# mippe_base_v2.net
KiCad netlist of a schematic drawn in EAGLE
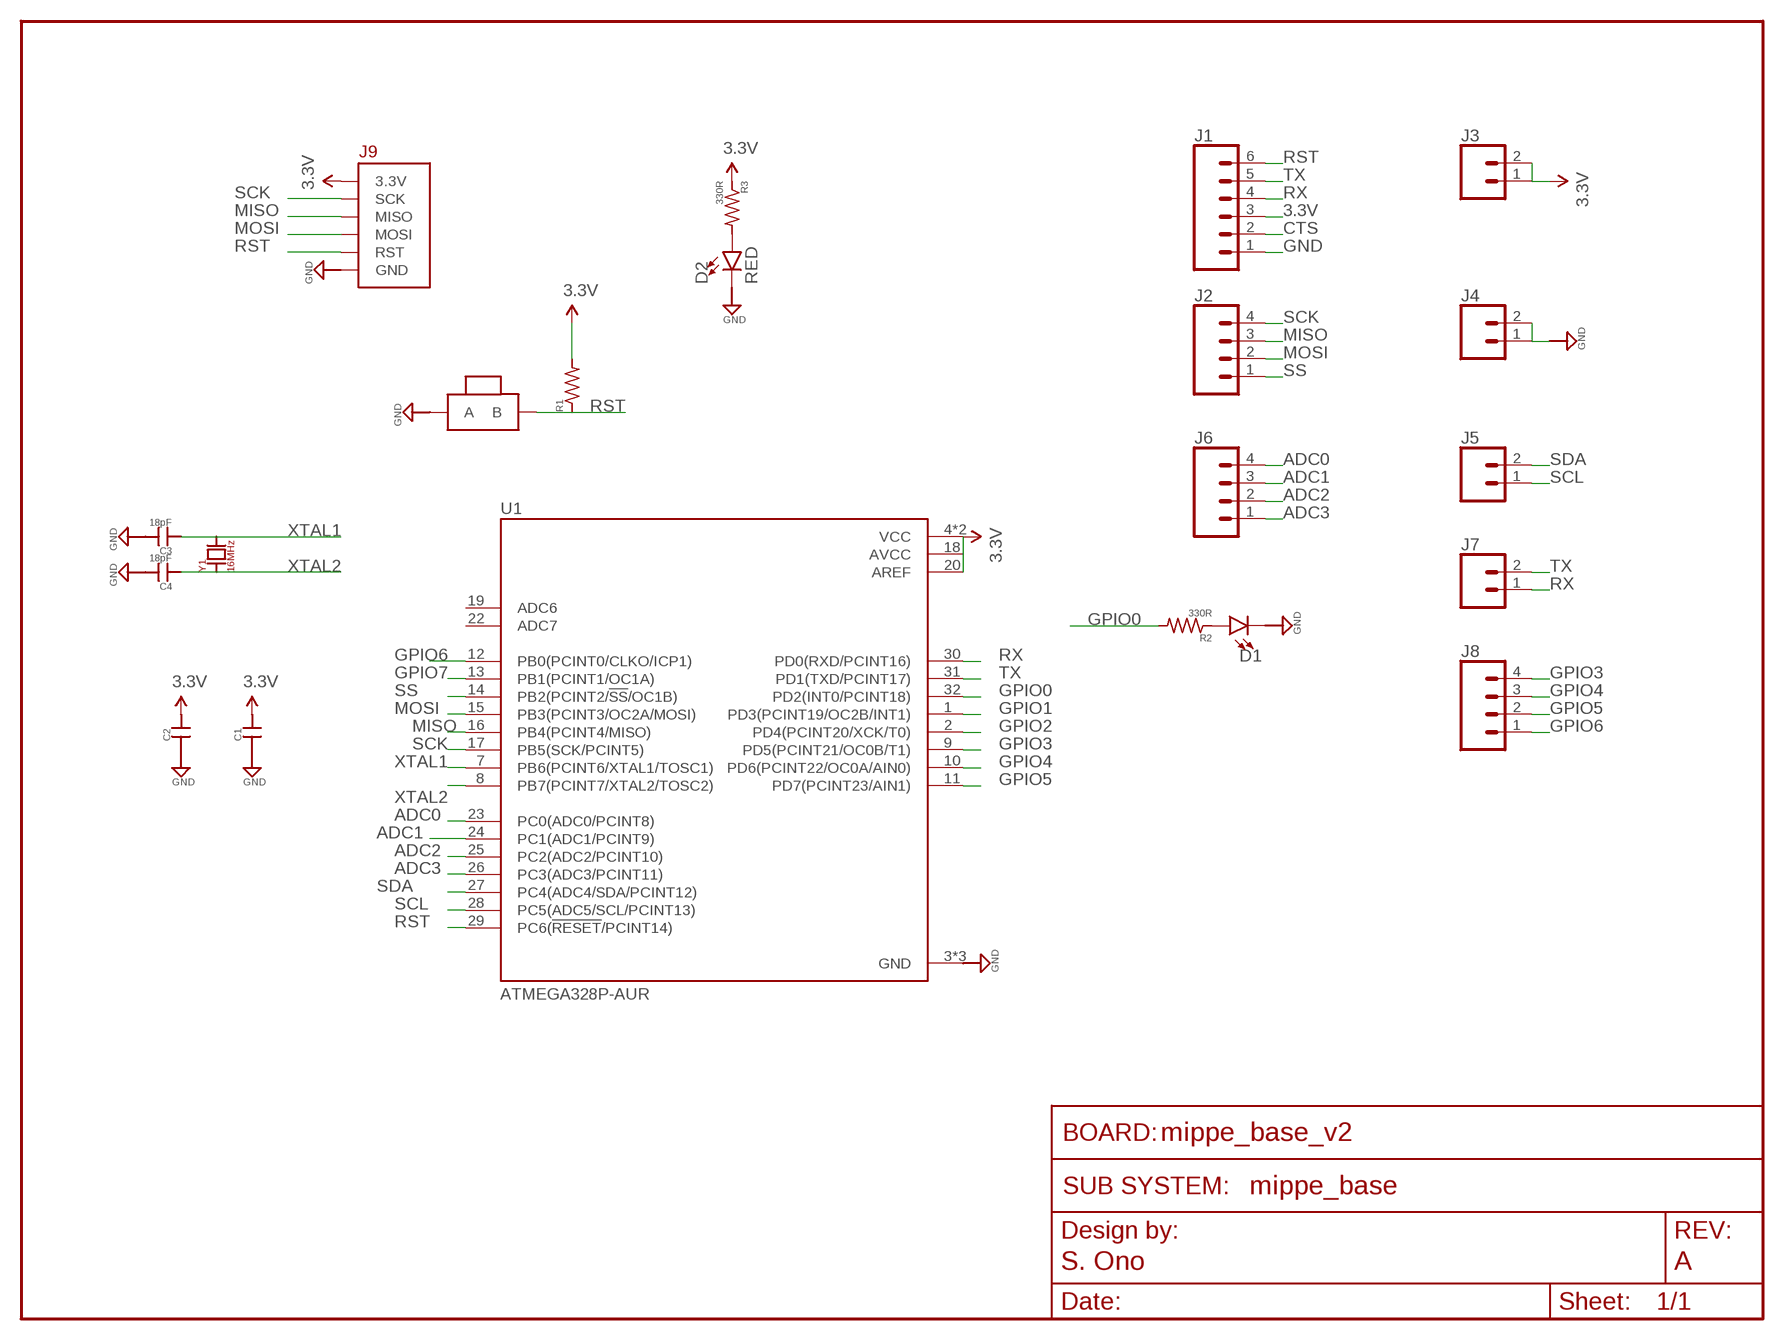
[diagram p0: schematic, sheet 1]

(export (version "E")
  (design (tool "Eeschema 10.0.6"))
  (components
    (comp (ref "C1")
      (value "CAP0603-CAP")
      (footprint "eagle-import:0603-CAP")
      (libsource (lib "eagle-import") (part "CAP0603-CAP"))
    )
    (comp (ref "C2")
      (value "CAP0603-CAP")
      (footprint "eagle-import:0603-CAP")
      (libsource (lib "eagle-import") (part "CAP0603-CAP"))
    )
    (comp (ref "C3")
      (value "18pF")
      (footprint "eagle-import:0603-CAP")
      (libsource (lib "eagle-import") (part "CAP0603-CAP"))
    )
    (comp (ref "C4")
      (value "18pF")
      (footprint "eagle-import:0603-CAP")
      (libsource (lib "eagle-import") (part "CAP0603-CAP"))
    )
    (comp (ref "D1")
      (value "LED0603")
      (footprint "eagle-import:LED-0603")
      (libsource (lib "eagle-import") (part "LED0603"))
    )
    (comp (ref "D2")
      (value "RED")
      (footprint "eagle-import:LED-0603")
      (libsource (lib "eagle-import") (part "LED0603"))
    )
    (comp (ref "J1")
      (value "CONN_06NO_SILK_FEMALE_PTH")
      (footprint "eagle-import:1X06_NO_SILK")
      (libsource (lib "eagle-import") (part "CONN_06NO_SILK_FEMALE_PTH"))
    )
    (comp (ref "J2")
      (value "CONN_041X04_NO_SILK")
      (footprint "eagle-import:1X04_NO_SILK")
      (libsource (lib "eagle-import") (part "CONN_041X04_NO_SILK"))
    )
    (comp (ref "J3")
      (value "CONN_021X02_NO_SILK")
      (footprint "eagle-import:1X02_NO_SILK")
      (libsource (lib "eagle-import") (part "CONN_021X02_NO_SILK"))
    )
    (comp (ref "J4")
      (value "CONN_021X02_NO_SILK")
      (footprint "eagle-import:1X02_NO_SILK")
      (libsource (lib "eagle-import") (part "CONN_021X02_NO_SILK"))
    )
    (comp (ref "J5")
      (value "CONN_021X02_NO_SILK")
      (footprint "eagle-import:1X02_NO_SILK")
      (libsource (lib "eagle-import") (part "CONN_021X02_NO_SILK"))
    )
    (comp (ref "J6")
      (value "CONN_041X04_NO_SILK")
      (footprint "eagle-import:1X04_NO_SILK")
      (libsource (lib "eagle-import") (part "CONN_041X04_NO_SILK"))
    )
    (comp (ref "J7")
      (value "CONN_021X02_NO_SILK")
      (footprint "eagle-import:1X02_NO_SILK")
      (libsource (lib "eagle-import") (part "CONN_021X02_NO_SILK"))
    )
    (comp (ref "J8")
      (value "CONN_041X04_NO_SILK")
      (footprint "eagle-import:1X04_NO_SILK")
      (libsource (lib "eagle-import") (part "CONN_041X04_NO_SILK"))
    )
    (comp (ref "J9")
      (value "BURNIN")
      (footprint "eagle-import:BURNIN")
      (libsource (lib "eagle-import") (part "BURNIN"))
    )
    (comp (ref "R1")
      (value "R-US_R0603")
      (footprint "eagle-import:R0603")
      (fields (field (name "MANUFACTURER") "Rohm Semiconductor"))
      (libsource (lib "eagle-import") (part "R-US_R0603"))
    )
    (comp (ref "R2")
      (value "330R")
      (footprint "eagle-import:R0603")
      (fields (field (name "MANUFACTURER") "Rohm Semiconductor"))
      (libsource (lib "eagle-import") (part "R-US_R0603"))
    )
    (comp (ref "R3")
      (value "330R")
      (footprint "eagle-import:R0603")
      (fields (field (name "MANUFACTURER") "Rohm Semiconductor"))
      (libsource (lib "eagle-import") (part "R-US_R0603"))
    )
    (comp (ref "SW1")
      (value "BTN-PTS810")
      (footprint "eagle-import:BTN_PTS810")
      (libsource (lib "eagle-import") (part "BTN-PTS810"))
    )
    (comp (ref "U1")
      (value "ATMEGA328P-AUR")
      (footprint "eagle-import:QFP80P900X900X120-32N")
      (fields (field (name "DIGI-KEY_PART_NUMBER") "ATMEGA328P-AURCT-ND") (field (name "MF") "Microchip"))
      (libsource (lib "eagle-import") (part "ATMEGA328P-AUR"))
    )
    (comp (ref "Y1")
      (value "16MHz")
      (footprint "eagle-import:XTAL500X320X130N")
      (libsource (lib "eagle-import") (part "CRYSTAL_SMOL"))
    )
  )
  (nets
    (net (code "1") (name "/ADC0") (class "Default")
      (node (ref "J6") (pin "4") (pinfunction "4_4") (pintype "passive"))
      (node (ref "U1") (pin "23") (pinfunction "PC0(ADC0/PCINT8)_23") (pintype "bidirectional"))
    )
    (net (code "2") (name "/ADC1") (class "Default")
      (node (ref "J6") (pin "3") (pinfunction "3_3") (pintype "passive"))
      (node (ref "U1") (pin "24") (pinfunction "PC1(ADC1/PCINT9)_24") (pintype "bidirectional"))
    )
    (net (code "3") (name "/ADC2") (class "Default")
      (node (ref "J6") (pin "2") (pinfunction "2_2") (pintype "passive"))
      (node (ref "U1") (pin "25") (pinfunction "PC2(ADC2/PCINT10)_25") (pintype "bidirectional"))
    )
    (net (code "4") (name "/ADC3") (class "Default")
      (node (ref "J6") (pin "1") (pinfunction "1_1") (pintype "passive"))
      (node (ref "U1") (pin "26") (pinfunction "PC3(ADC3/PCINT11)_26") (pintype "bidirectional"))
    )
    (net (code "5") (name "/CTS") (class "Default")
      (node (ref "J1") (pin "2") (pinfunction "2_2") (pintype "passive"))
    )
    (net (code "6") (name "/GPIO0") (class "Default")
      (node (ref "R2") (pin "2") (pinfunction "2_2") (pintype "passive"))
      (node (ref "U1") (pin "32") (pinfunction "PD2(INT0/PCINT18)_32") (pintype "bidirectional"))
    )
    (net (code "7") (name "/GPIO1") (class "Default")
      (node (ref "U1") (pin "1") (pinfunction "PD3(PCINT19/OC2B/INT1)_1") (pintype "bidirectional"))
    )
    (net (code "8") (name "/GPIO2") (class "Default")
      (node (ref "U1") (pin "2") (pinfunction "PD4(PCINT20/XCK/T0)_2") (pintype "bidirectional"))
    )
    (net (code "9") (name "/GPIO3") (class "Default")
      (node (ref "J8") (pin "4") (pinfunction "4_4") (pintype "passive"))
      (node (ref "U1") (pin "9") (pinfunction "PD5(PCINT21/OC0B/T1)_9") (pintype "bidirectional"))
    )
    (net (code "10") (name "/GPIO4") (class "Default")
      (node (ref "J8") (pin "3") (pinfunction "3_3") (pintype "passive"))
      (node (ref "U1") (pin "10") (pinfunction "PD6(PCINT22/OC0A/AIN0)_10") (pintype "bidirectional"))
    )
    (net (code "11") (name "/GPIO5") (class "Default")
      (node (ref "J8") (pin "2") (pinfunction "2_2") (pintype "passive"))
      (node (ref "U1") (pin "11") (pinfunction "PD7(PCINT23/AIN1)_11") (pintype "bidirectional"))
    )
    (net (code "12") (name "/GPIO6") (class "Default")
      (node (ref "J8") (pin "1") (pinfunction "1_1") (pintype "passive"))
      (node (ref "U1") (pin "12") (pinfunction "PB0(PCINT0/CLKO/ICP1)_12") (pintype "bidirectional"))
    )
    (net (code "13") (name "/GPIO7") (class "Default")
      (node (ref "U1") (pin "13") (pinfunction "PB1(PCINT1/OC1A)_13") (pintype "bidirectional"))
    )
    (net (code "14") (name "/MISO") (class "Default")
      (node (ref "J2") (pin "3") (pinfunction "3_3") (pintype "passive"))
      (node (ref "J9") (pin "MISO") (pinfunction "MISO_MISO") (pintype "bidirectional"))
      (node (ref "U1") (pin "16") (pinfunction "PB4(PCINT4/MISO)_16") (pintype "bidirectional"))
    )
    (net (code "15") (name "/MOSI") (class "Default")
      (node (ref "J2") (pin "2") (pinfunction "2_2") (pintype "passive"))
      (node (ref "J9") (pin "MOSI") (pinfunction "MOSI_MOSI") (pintype "bidirectional"))
      (node (ref "U1") (pin "15") (pinfunction "PB3(PCINT3/OC2A/MOSI)_15") (pintype "bidirectional"))
    )
    (net (code "16") (name "/RST") (class "Default")
      (node (ref "J1") (pin "6") (pinfunction "6_6") (pintype "passive"))
      (node (ref "J9") (pin "RST") (pinfunction "RST_RST") (pintype "bidirectional"))
      (node (ref "R1") (pin "1") (pinfunction "1_1") (pintype "passive"))
      (node (ref "SW1") (pin "3") (pinfunction "B_3") (pintype "bidirectional"))
      (node (ref "SW1") (pin "4") (pinfunction "B_4") (pintype "bidirectional"))
      (node (ref "U1") (pin "29") (pinfunction "PC6(~{RESET}/PCINT14)_29") (pintype "bidirectional"))
    )
    (net (code "17") (name "/RX") (class "Default")
      (node (ref "J1") (pin "4") (pinfunction "4_4") (pintype "passive"))
      (node (ref "J7") (pin "1") (pinfunction "1_1") (pintype "passive"))
      (node (ref "U1") (pin "30") (pinfunction "PD0(RXD/PCINT16)_30") (pintype "bidirectional"))
    )
    (net (code "18") (name "/SCK") (class "Default")
      (node (ref "J2") (pin "4") (pinfunction "4_4") (pintype "passive"))
      (node (ref "J9") (pin "SCK") (pinfunction "SCK_SCK") (pintype "bidirectional"))
      (node (ref "U1") (pin "17") (pinfunction "PB5(SCK/PCINT5)_17") (pintype "bidirectional"))
    )
    (net (code "19") (name "/SCL") (class "Default")
      (node (ref "J5") (pin "1") (pinfunction "1_1") (pintype "passive"))
      (node (ref "U1") (pin "28") (pinfunction "PC5(ADC5/SCL/PCINT13)_28") (pintype "bidirectional"))
    )
    (net (code "20") (name "/SDA") (class "Default")
      (node (ref "J5") (pin "2") (pinfunction "2_2") (pintype "passive"))
      (node (ref "U1") (pin "27") (pinfunction "PC4(ADC4/SDA/PCINT12)_27") (pintype "bidirectional"))
    )
    (net (code "21") (name "/SS") (class "Default")
      (node (ref "J2") (pin "1") (pinfunction "1_1") (pintype "passive"))
      (node (ref "U1") (pin "14") (pinfunction "PB2(PCINT2/~{SS}/OC1B)_14") (pintype "bidirectional"))
    )
    (net (code "22") (name "/TX") (class "Default")
      (node (ref "J1") (pin "5") (pinfunction "5_5") (pintype "passive"))
      (node (ref "J7") (pin "2") (pinfunction "2_2") (pintype "passive"))
      (node (ref "U1") (pin "31") (pinfunction "PD1(TXD/PCINT17)_31") (pintype "bidirectional"))
    )
    (net (code "23") (name "/XTAL1") (class "Default")
      (node (ref "C3") (pin "1") (pinfunction "1_1") (pintype "passive"))
      (node (ref "U1") (pin "7") (pinfunction "PB6(PCINT6/XTAL1/TOSC1)_7") (pintype "bidirectional"))
      (node (ref "Y1") (pin "2") (pinfunction "B_2") (pintype "passive"))
    )
    (net (code "24") (name "/XTAL2") (class "Default")
      (node (ref "C4") (pin "1") (pinfunction "1_1") (pintype "passive"))
      (node (ref "U1") (pin "8") (pinfunction "PB7(PCINT7/XTAL2/TOSC2)_8") (pintype "bidirectional"))
      (node (ref "Y1") (pin "1") (pinfunction "A_1") (pintype "passive"))
    )
    (net (code "25") (name "3.3V") (class "Default")
      (node (ref "C1") (pin "2") (pinfunction "2_2") (pintype "passive"))
      (node (ref "C2") (pin "2") (pinfunction "2_2") (pintype "passive"))
      (node (ref "J1") (pin "3") (pinfunction "3_3") (pintype "passive"))
      (node (ref "J3") (pin "1") (pinfunction "1_1") (pintype "passive"))
      (node (ref "J3") (pin "2") (pinfunction "2_2") (pintype "passive"))
      (node (ref "J9") (pin "3.3V") (pinfunction "3.3V_3.3V") (pintype "power_in"))
      (node (ref "R1") (pin "2") (pinfunction "2_2") (pintype "passive"))
      (node (ref "R3") (pin "1") (pinfunction "1_1") (pintype "passive"))
      (node (ref "U1") (pin "18") (pinfunction "AVCC_18") (pintype "power_in"))
      (node (ref "U1") (pin "20") (pinfunction "AREF_20") (pintype "power_in"))
      (node (ref "U1") (pin "4") (pinfunction "VCC_4") (pintype "power_in"))
      (node (ref "U1") (pin "6") (pinfunction "VCC_6") (pintype "power_in"))
    )
    (net (code "26") (name "GND") (class "Default")
      (node (ref "C1") (pin "1") (pinfunction "1_1") (pintype "passive"))
      (node (ref "C2") (pin "1") (pinfunction "1_1") (pintype "passive"))
      (node (ref "C3") (pin "2") (pinfunction "2_2") (pintype "passive"))
      (node (ref "C4") (pin "2") (pinfunction "2_2") (pintype "passive"))
      (node (ref "D1") (pin "C") (pinfunction "C_C") (pintype "passive"))
      (node (ref "D2") (pin "C") (pinfunction "C_C") (pintype "passive"))
      (node (ref "J1") (pin "1") (pinfunction "1_1") (pintype "passive"))
      (node (ref "J4") (pin "1") (pinfunction "1_1") (pintype "passive"))
      (node (ref "J4") (pin "2") (pinfunction "2_2") (pintype "passive"))
      (node (ref "J9") (pin "GND") (pinfunction "GND_GND") (pintype "power_in"))
      (node (ref "SW1") (pin "1") (pinfunction "A_1") (pintype "bidirectional"))
      (node (ref "SW1") (pin "2") (pinfunction "A_2") (pintype "bidirectional"))
      (node (ref "U1") (pin "21") (pinfunction "GND_21") (pintype "power_in"))
      (node (ref "U1") (pin "3") (pinfunction "GND_3") (pintype "power_in"))
      (node (ref "U1") (pin "5") (pinfunction "GND_5") (pintype "power_in"))
    )
    (net (code "27") (name "Net-(D1-PadA)") (class "Default")
      (node (ref "D1") (pin "A") (pinfunction "A_A") (pintype "passive"))
      (node (ref "R2") (pin "1") (pinfunction "1_1") (pintype "passive"))
    )
    (net (code "28") (name "Net-(D2-PadA)") (class "Default")
      (node (ref "D2") (pin "A") (pinfunction "A_A") (pintype "passive"))
      (node (ref "R3") (pin "2") (pinfunction "2_2") (pintype "passive"))
    )
    (net (code "29") (name "unconnected-(U1-ADC6-Pad19)") (class "Default")
      (node (ref "U1") (pin "19") (pinfunction "ADC6_19") (pintype "input"))
    )
    (net (code "30") (name "unconnected-(U1-ADC7-Pad22)") (class "Default")
      (node (ref "U1") (pin "22") (pinfunction "ADC7_22") (pintype "input"))
    )
  )
)
